# 3DR-GPS_mag-LEA6-v12.net
KiCad netlist of a schematic drawn in EAGLE
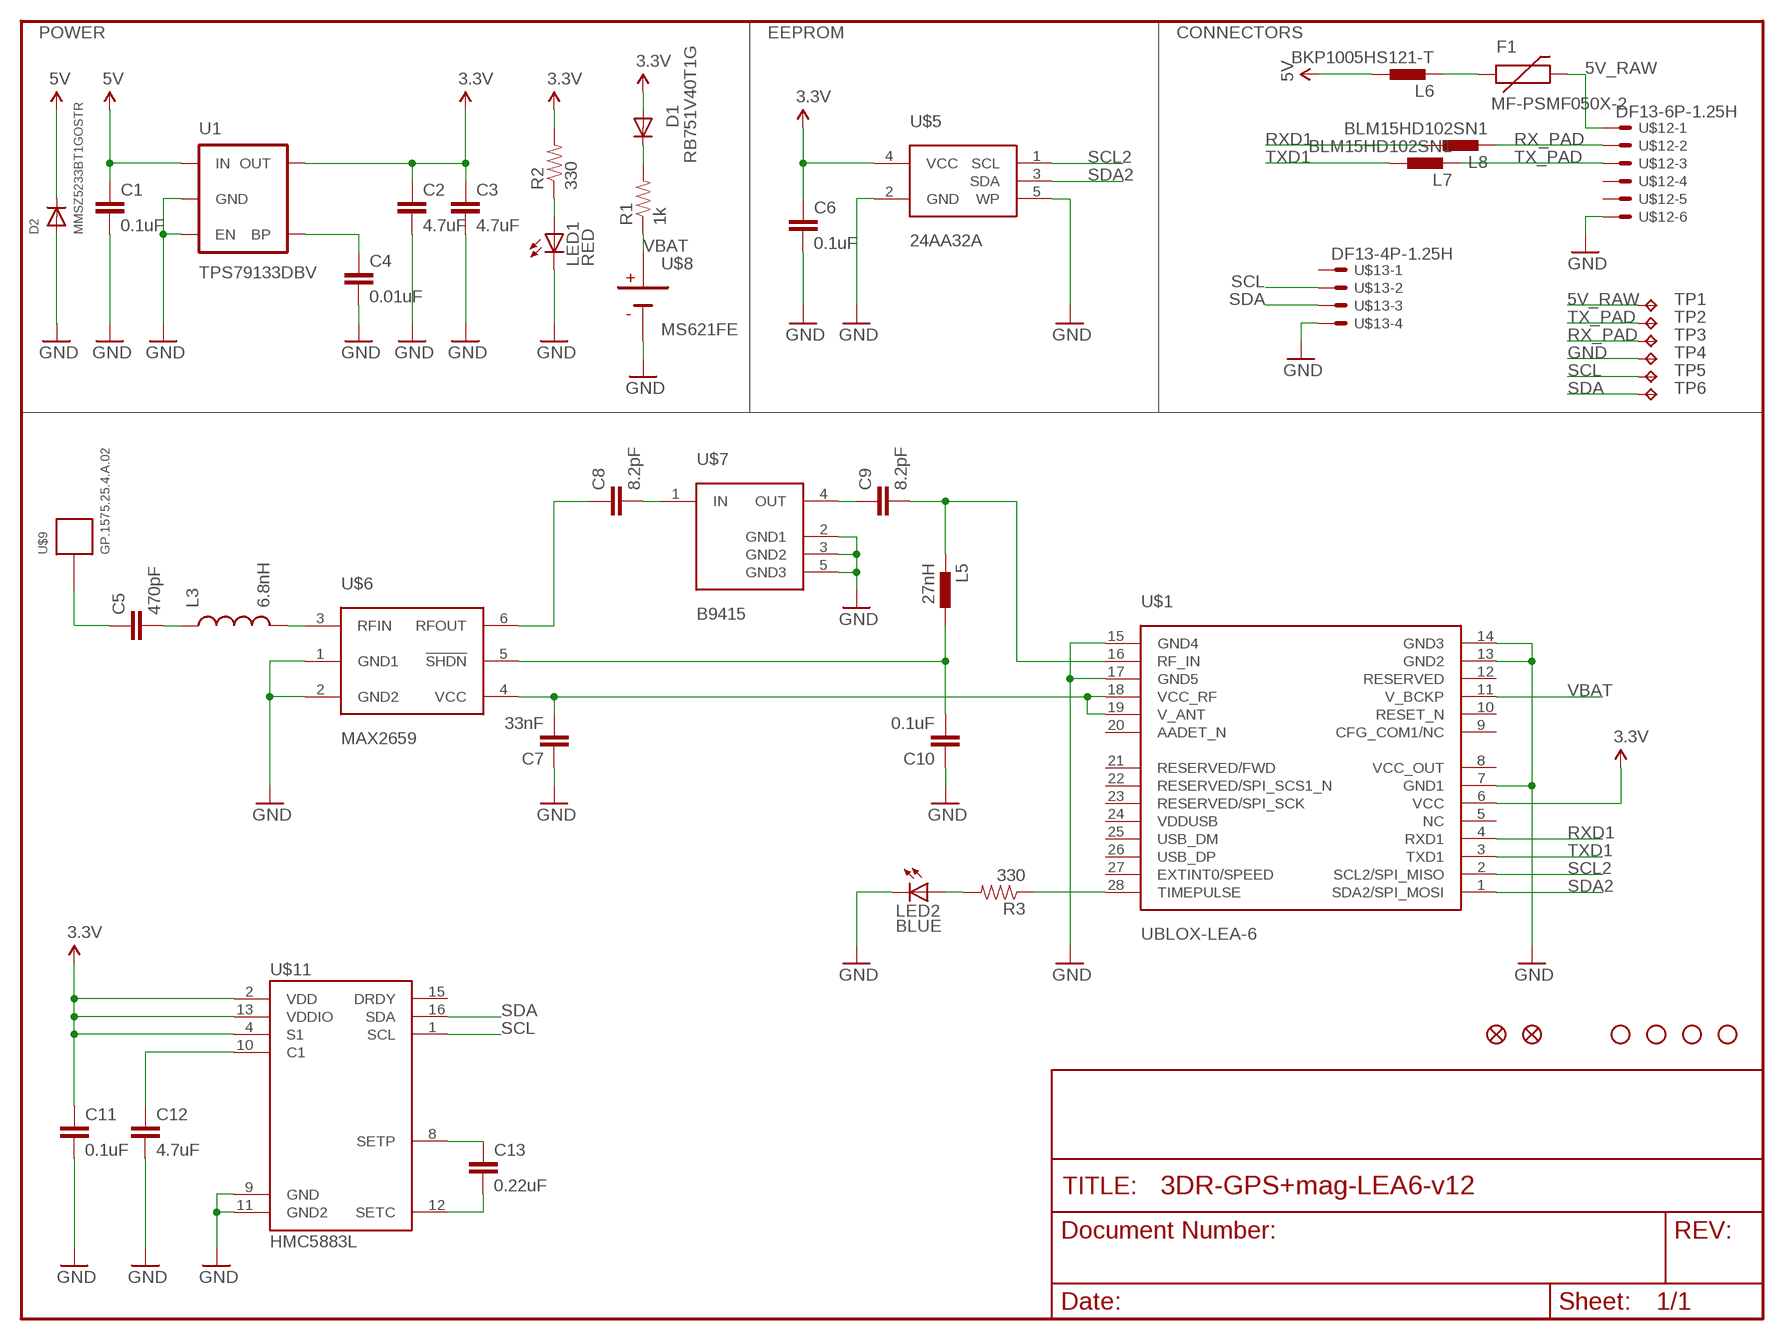
[diagram p0: schematic, sheet 1]

(export (version "E")
  (design (tool "Eeschema 10.0.6"))
  (components
    (comp (ref "C1")
      (value "0.1uF")
      (footprint "eagle-import:0402-CAP")
      (libsource (lib "eagle-import") (part "CAP0402-CAP"))
    )
    (comp (ref "C2")
      (value "4.7uF")
      (footprint "eagle-import:0805")
      (libsource (lib "eagle-import") (part "CAP0805"))
    )
    (comp (ref "C3")
      (value "4.7uF")
      (footprint "eagle-import:0805")
      (libsource (lib "eagle-import") (part "CAP0805"))
    )
    (comp (ref "C4")
      (value "0.01uF")
      (footprint "eagle-import:0402-CAP")
      (libsource (lib "eagle-import") (part "CAP0402-CAP"))
    )
    (comp (ref "C5")
      (value "470pF")
      (footprint "eagle-import:0402-CAP")
      (libsource (lib "eagle-import") (part "CAP0402-CAP"))
    )
    (comp (ref "C6")
      (value "0.1uF")
      (footprint "eagle-import:0402-CAP")
      (libsource (lib "eagle-import") (part "CAP0402-CAP"))
    )
    (comp (ref "C7")
      (value "33nF")
      (footprint "eagle-import:0402-CAP")
      (libsource (lib "eagle-import") (part "CAP0402-CAP"))
    )
    (comp (ref "C8")
      (value "8.2pF")
      (footprint "eagle-import:0402-CAP")
      (libsource (lib "eagle-import") (part "CAP0402-CAP"))
    )
    (comp (ref "C9")
      (value "8.2pF")
      (footprint "eagle-import:0402-CAP")
      (libsource (lib "eagle-import") (part "CAP0402-CAP"))
    )
    (comp (ref "C10")
      (value "0.1uF")
      (footprint "eagle-import:0402-CAP")
      (libsource (lib "eagle-import") (part "CAP0402-CAP"))
    )
    (comp (ref "C11")
      (value "0.1uF")
      (footprint "eagle-import:0402-CAP")
      (libsource (lib "eagle-import") (part "CAP0402-CAP"))
    )
    (comp (ref "C12")
      (value "4.7uF")
      (footprint "eagle-import:1206")
      (libsource (lib "eagle-import") (part "CAP1206"))
    )
    (comp (ref "C13")
      (value "0.22uF")
      (footprint "eagle-import:0402-CAP")
      (libsource (lib "eagle-import") (part "CAP0402-CAP"))
    )
    (comp (ref "D1")
      (value "RB751V40T1G")
      (footprint "eagle-import:SOD-323")
      (libsource (lib "eagle-import") (part "DIODESOD"))
    )
    (comp (ref "D2")
      (value "MMSZ5233BT1GOSTR")
      (footprint "eagle-import:SOD-123")
      (libsource (lib "eagle-import") (part "DIODESOD-123"))
    )
    (comp (ref "F1")
      (value "MF-PSMF050X-2")
      (footprint "eagle-import:0805")
      (libsource (lib "eagle-import") (part "PTC"))
    )
    (comp (ref "JP1")
      (value "FIDUCIAL1X2")
      (footprint "eagle-import:FIDUCIAL-1X2")
      (libsource (lib "eagle-import") (part "FIDUCIAL1X2"))
    )
    (comp (ref "JP2")
      (value "FIDUCIAL1X2")
      (footprint "eagle-import:FIDUCIAL-1X2")
      (libsource (lib "eagle-import") (part "FIDUCIAL1X2"))
    )
    (comp (ref "JP3")
      (value "STAND-OFF")
      (footprint "eagle-import:STAND-OFF")
      (libsource (lib "eagle-import") (part "STAND-OFF"))
    )
    (comp (ref "JP4")
      (value "STAND-OFF")
      (footprint "eagle-import:STAND-OFF")
      (libsource (lib "eagle-import") (part "STAND-OFF"))
    )
    (comp (ref "JP5")
      (value "STAND-OFF")
      (footprint "eagle-import:STAND-OFF")
      (libsource (lib "eagle-import") (part "STAND-OFF"))
    )
    (comp (ref "JP6")
      (value "STAND-OFF")
      (footprint "eagle-import:STAND-OFF")
      (libsource (lib "eagle-import") (part "STAND-OFF"))
    )
    (comp (ref "L3")
      (value "6.8nH")
      (footprint "eagle-import:C0402")
      (libsource (lib "eagle-import") (part "INDUCTOR0402"))
    )
    (comp (ref "L5")
      (value "27nH")
      (footprint "eagle-import:0402-IND")
      (libsource (lib "eagle-import") (part "INDUCTOR-0402"))
    )
    (comp (ref "L6")
      (value "BKP1005HS121-T")
      (footprint "eagle-import:0402-IND")
      (libsource (lib "eagle-import") (part "INDUCTOR-0402"))
    )
    (comp (ref "L7")
      (value "BLM15HD102SN1")
      (footprint "eagle-import:0402-IND")
      (libsource (lib "eagle-import") (part "INDUCTOR-0402"))
    )
    (comp (ref "L8")
      (value "BLM15HD102SN1")
      (footprint "eagle-import:0402-IND")
      (libsource (lib "eagle-import") (part "INDUCTOR-0402"))
    )
    (comp (ref "LED1")
      (value "RED")
      (footprint "eagle-import:LED-0603")
      (libsource (lib "eagle-import") (part "LED0603"))
    )
    (comp (ref "LED2")
      (value "BLUE")
      (footprint "eagle-import:LED-0603")
      (libsource (lib "eagle-import") (part "LED0603"))
    )
    (comp (ref "R1")
      (value "1k")
      (footprint "eagle-import:0402-RES")
      (libsource (lib "eagle-import") (part "RESISTOR0402-RES"))
    )
    (comp (ref "R2")
      (value "330")
      (footprint "eagle-import:0402-RES")
      (libsource (lib "eagle-import") (part "RESISTOR0402-RES"))
    )
    (comp (ref "R3")
      (value "330")
      (footprint "eagle-import:0402-RES")
      (libsource (lib "eagle-import") (part "RESISTOR0402-RES"))
    )
    (comp (ref "TP1")
      (value "TPTP20SQ")
      (footprint "eagle-import:TP20SQ")
      (libsource (lib "eagle-import") (part "TPTP20SQ"))
    )
    (comp (ref "TP2")
      (value "TPTP20SQ")
      (footprint "eagle-import:TP20SQ")
      (libsource (lib "eagle-import") (part "TPTP20SQ"))
    )
    (comp (ref "TP3")
      (value "TPTP20SQ")
      (footprint "eagle-import:TP20SQ")
      (libsource (lib "eagle-import") (part "TPTP20SQ"))
    )
    (comp (ref "TP4")
      (value "TPTP20SQ")
      (footprint "eagle-import:TP20SQ")
      (libsource (lib "eagle-import") (part "TPTP20SQ"))
    )
    (comp (ref "TP5")
      (value "TPTP20SQ")
      (footprint "eagle-import:TP20SQ")
      (libsource (lib "eagle-import") (part "TPTP20SQ"))
    )
    (comp (ref "TP6")
      (value "TPTP20SQ")
      (footprint "eagle-import:TP20SQ")
      (libsource (lib "eagle-import") (part "TPTP20SQ"))
    )
    (comp (ref "U$1")
      (value "UBLOX-LEA-6")
      (footprint "eagle-import:UBLOX-LEA")
      (libsource (lib "eagle-import") (part "UBLOX-LEA-6"))
    )
    (comp (ref "U$5")
      (value "24AA32A")
      (footprint "eagle-import:SOT23-5")
      (libsource (lib "eagle-import") (part "24AA32A"))
    )
    (comp (ref "U$6")
      (value "MAX2659")
      (footprint "eagle-import:UDFN-6")
      (libsource (lib "eagle-import") (part "MAX2659"))
    )
    (comp (ref "U$7")
      (value "B9415")
      (footprint "eagle-import:GPS-RF-SAW-FILTER")
      (fields (field (name "MFGPN") "B9415"))
      (libsource (lib "eagle-import") (part "B9415"))
    )
    (comp (ref "U$8")
      (value "MS621FE")
      (footprint "eagle-import:MS621FE")
      (libsource (lib "eagle-import") (part "MS621FE"))
    )
    (comp (ref "U$9")
      (value "GP.1575.25.4.A.02")
      (footprint "eagle-import:GP.1575.25.4.A.02")
      (libsource (lib "eagle-import") (part "GP.1575.25.4.A.02"))
    )
    (comp (ref "U$11")
      (value "HMC5883L")
      (footprint "eagle-import:LPCC16")
      (libsource (lib "eagle-import") (part "HMC5883L"))
    )
    (comp (ref "U$12")
      (value "DF13-6P-1.25H")
      (footprint "eagle-import:DF13A-6P-1.25H")
      (libsource (lib "eagle-import") (part "DF13-6P-1.25?H"))
    )
    (comp (ref "U$13")
      (value "DF13-4P-1.25H")
      (footprint "eagle-import:DF13A-4P-1.25H")
      (libsource (lib "eagle-import") (part "DF13-4P-1.25?H"))
    )
    (comp (ref "U1")
      (value "TPS79133DBV")
      (footprint "eagle-import:SOT23-5")
      (libsource (lib "eagle-import") (part "V_REG_LDOSMD"))
    )
  )
  (nets
    (net (code "1") (name "/5V_RAW") (class "Default")
      (node (ref "F1") (pin "2") (pinfunction "2_2") (pintype "bidirectional"))
      (node (ref "TP1") (pin "TP") (pinfunction "TP_TP") (pintype "input"))
      (node (ref "U$12") (pin "1") (pinfunction "S_1") (pintype "passive"))
    )
    (net (code "2") (name "/RXD1") (class "Default")
      (node (ref "L8") (pin "P$1") (pinfunction "1_P$1") (pintype "passive"))
      (node (ref "U$1") (pin "4") (pinfunction "RXD1_4") (pintype "bidirectional"))
    )
    (net (code "3") (name "/RX_PAD") (class "Default")
      (node (ref "L8") (pin "P$2") (pinfunction "2_P$2") (pintype "passive"))
      (node (ref "TP3") (pin "TP") (pinfunction "TP_TP") (pintype "input"))
      (node (ref "U$12") (pin "2") (pinfunction "S_2") (pintype "passive"))
    )
    (net (code "4") (name "/SCL") (class "Default")
      (node (ref "TP5") (pin "TP") (pinfunction "TP_TP") (pintype "input"))
      (node (ref "U$11") (pin "1") (pinfunction "SCL_1") (pintype "bidirectional"))
      (node (ref "U$13") (pin "2") (pinfunction "S_2") (pintype "passive"))
    )
    (net (code "5") (name "/SCL2") (class "Default")
      (node (ref "U$1") (pin "2") (pinfunction "SCL2/SPI_MISO_2") (pintype "bidirectional"))
      (node (ref "U$5") (pin "1") (pinfunction "SCL_1") (pintype "bidirectional"))
    )
    (net (code "6") (name "/SDA") (class "Default")
      (node (ref "TP6") (pin "TP") (pinfunction "TP_TP") (pintype "input"))
      (node (ref "U$11") (pin "16") (pinfunction "SDA_16") (pintype "bidirectional"))
      (node (ref "U$13") (pin "3") (pinfunction "S_3") (pintype "passive"))
    )
    (net (code "7") (name "/SDA2") (class "Default")
      (node (ref "U$1") (pin "1") (pinfunction "SDA2/SPI_MOSI_1") (pintype "bidirectional"))
      (node (ref "U$5") (pin "3") (pinfunction "SDA_3") (pintype "bidirectional"))
    )
    (net (code "8") (name "/TXD1") (class "Default")
      (node (ref "L7") (pin "P$1") (pinfunction "1_P$1") (pintype "passive"))
      (node (ref "U$1") (pin "3") (pinfunction "TXD1_3") (pintype "bidirectional"))
    )
    (net (code "9") (name "/TX_PAD") (class "Default")
      (node (ref "L7") (pin "P$2") (pinfunction "2_P$2") (pintype "passive"))
      (node (ref "TP2") (pin "TP") (pinfunction "TP_TP") (pintype "input"))
      (node (ref "U$12") (pin "3") (pinfunction "S_3") (pintype "passive"))
    )
    (net (code "10") (name "/VBAT") (class "Default")
      (node (ref "R1") (pin "1") (pinfunction "1_1") (pintype "passive"))
      (node (ref "U$1") (pin "11") (pinfunction "V_BCKP_11") (pintype "bidirectional"))
      (node (ref "U$8") (pin "1") (pinfunction "POS_1") (pintype "bidirectional"))
    )
    (net (code "11") (name "3.3V") (class "Default")
      (node (ref "C11") (pin "1") (pinfunction "1_1") (pintype "passive"))
      (node (ref "C2") (pin "1") (pinfunction "1_1") (pintype "passive"))
      (node (ref "C3") (pin "1") (pinfunction "1_1") (pintype "passive"))
      (node (ref "C6") (pin "1") (pinfunction "1_1") (pintype "passive"))
      (node (ref "D1") (pin "2") (pinfunction "A_2") (pintype "passive"))
      (node (ref "R2") (pin "2") (pinfunction "2_2") (pintype "passive"))
      (node (ref "U$1") (pin "6") (pinfunction "VCC_6") (pintype "bidirectional"))
      (node (ref "U$11") (pin "13") (pinfunction "VDDIO_13") (pintype "bidirectional"))
      (node (ref "U$11") (pin "2") (pinfunction "VDD_2") (pintype "bidirectional"))
      (node (ref "U$11") (pin "4") (pinfunction "S1_4") (pintype "bidirectional"))
      (node (ref "U$5") (pin "4") (pinfunction "VCC_4") (pintype "bidirectional"))
      (node (ref "U1") (pin "5") (pinfunction "OUT_5") (pintype "passive"))
    )
    (net (code "12") (name "5V") (class "Default")
      (node (ref "C1") (pin "1") (pinfunction "1_1") (pintype "passive"))
      (node (ref "D2") (pin "C") (pinfunction "C_C") (pintype "passive"))
      (node (ref "L6") (pin "P$1") (pinfunction "1_P$1") (pintype "passive"))
      (node (ref "U1") (pin "1") (pinfunction "IN_1") (pintype "input"))
    )
    (net (code "13") (name "GND") (class "Default")
      (node (ref "C1") (pin "2") (pinfunction "2_2") (pintype "passive"))
      (node (ref "C10") (pin "1") (pinfunction "1_1") (pintype "passive"))
      (node (ref "C11") (pin "2") (pinfunction "2_2") (pintype "passive"))
      (node (ref "C12") (pin "2") (pinfunction "2_2") (pintype "passive"))
      (node (ref "C2") (pin "2") (pinfunction "2_2") (pintype "passive"))
      (node (ref "C3") (pin "2") (pinfunction "2_2") (pintype "passive"))
      (node (ref "C4") (pin "2") (pinfunction "2_2") (pintype "passive"))
      (node (ref "C6") (pin "2") (pinfunction "2_2") (pintype "passive"))
      (node (ref "C7") (pin "1") (pinfunction "1_1") (pintype "passive"))
      (node (ref "D2") (pin "A") (pinfunction "A_A") (pintype "passive"))
      (node (ref "LED1") (pin "C") (pinfunction "C_C") (pintype "passive"))
      (node (ref "LED2") (pin "C") (pinfunction "C_C") (pintype "passive"))
      (node (ref "TP4") (pin "TP") (pinfunction "TP_TP") (pintype "input"))
      (node (ref "U$1") (pin "13") (pinfunction "GND2_13") (pintype "bidirectional"))
      (node (ref "U$1") (pin "14") (pinfunction "GND3_14") (pintype "bidirectional"))
      (node (ref "U$1") (pin "15") (pinfunction "GND4_15") (pintype "bidirectional"))
      (node (ref "U$1") (pin "17") (pinfunction "GND5_17") (pintype "bidirectional"))
      (node (ref "U$1") (pin "7") (pinfunction "GND1_7") (pintype "bidirectional"))
      (node (ref "U$11") (pin "11") (pinfunction "GND2_11") (pintype "bidirectional"))
      (node (ref "U$11") (pin "9") (pinfunction "GND_9") (pintype "bidirectional"))
      (node (ref "U$12") (pin "6") (pinfunction "S_6") (pintype "passive"))
      (node (ref "U$13") (pin "4") (pinfunction "S_4") (pintype "passive"))
      (node (ref "U$5") (pin "2") (pinfunction "GND_2") (pintype "bidirectional"))
      (node (ref "U$5") (pin "5") (pinfunction "WP_5") (pintype "bidirectional"))
      (node (ref "U$6") (pin "1") (pinfunction "GND1_1") (pintype "bidirectional"))
      (node (ref "U$6") (pin "2") (pinfunction "GND2_2") (pintype "bidirectional"))
      (node (ref "U$7") (pin "2") (pinfunction "GND1_2") (pintype "bidirectional"))
      (node (ref "U$7") (pin "3") (pinfunction "GND2_3") (pintype "bidirectional"))
      (node (ref "U$7") (pin "5") (pinfunction "GND3_5") (pintype "bidirectional"))
      (node (ref "U$8") (pin "2") (pinfunction "NEG_2") (pintype "bidirectional"))
      (node (ref "U1") (pin "2") (pinfunction "GND_2") (pintype "input"))
      (node (ref "U1") (pin "3") (pinfunction "EN_3") (pintype "input"))
    )
    (net (code "14") (name "Net-(C5-Pad2)") (class "Default")
      (node (ref "C5") (pin "2") (pinfunction "2_2") (pintype "passive"))
      (node (ref "L3") (pin "1") (pinfunction "1_1") (pintype "passive"))
    )
    (net (code "15") (name "Net-(D1-C)") (class "Default")
      (node (ref "D1") (pin "1") (pinfunction "C_1") (pintype "passive"))
      (node (ref "R1") (pin "2") (pinfunction "2_2") (pintype "passive"))
    )
    (net (code "16") (name "Net-(L5-1)") (class "Default")
      (node (ref "C10") (pin "2") (pinfunction "2_2") (pintype "passive"))
      (node (ref "L5") (pin "P$1") (pinfunction "1_P$1") (pintype "passive"))
      (node (ref "U$6") (pin "5") (pinfunction "~{SHDN}_5") (pintype "bidirectional"))
    )
    (net (code "17") (name "Net-(L5-2)") (class "Default")
      (node (ref "C9") (pin "2") (pinfunction "2_2") (pintype "passive"))
      (node (ref "L5") (pin "P$2") (pinfunction "2_P$2") (pintype "passive"))
      (node (ref "U$1") (pin "16") (pinfunction "RF_IN_16") (pintype "bidirectional"))
    )
    (net (code "18") (name "Net-(L6-2)") (class "Default")
      (node (ref "F1") (pin "1") (pinfunction "1_1") (pintype "bidirectional"))
      (node (ref "L6") (pin "P$2") (pinfunction "2_P$2") (pintype "passive"))
    )
    (net (code "19") (name "Net-(LED1-PadA)") (class "Default")
      (node (ref "LED1") (pin "A") (pinfunction "A_A") (pintype "passive"))
      (node (ref "R2") (pin "1") (pinfunction "1_1") (pintype "passive"))
    )
    (net (code "20") (name "Net-(LED2-PadA)") (class "Default")
      (node (ref "LED2") (pin "A") (pinfunction "A_A") (pintype "passive"))
      (node (ref "R3") (pin "2") (pinfunction "2_2") (pintype "passive"))
    )
    (net (code "21") (name "Net-(U$1-TIMEPULSE)") (class "Default")
      (node (ref "R3") (pin "1") (pinfunction "1_1") (pintype "passive"))
      (node (ref "U$1") (pin "28") (pinfunction "TIMEPULSE_28") (pintype "bidirectional"))
    )
    (net (code "22") (name "Net-(U$1-VCC_RF)") (class "Default")
      (node (ref "C7") (pin "2") (pinfunction "2_2") (pintype "passive"))
      (node (ref "U$1") (pin "18") (pinfunction "VCC_RF_18") (pintype "bidirectional"))
      (node (ref "U$1") (pin "19") (pinfunction "V_ANT_19") (pintype "bidirectional"))
      (node (ref "U$6") (pin "4") (pinfunction "VCC_4") (pintype "bidirectional"))
    )
    (net (code "23") (name "Net-(U$6-RFIN)") (class "Default")
      (node (ref "L3") (pin "2") (pinfunction "2_2") (pintype "passive"))
      (node (ref "U$6") (pin "3") (pinfunction "RFIN_3") (pintype "bidirectional"))
    )
    (net (code "24") (name "Net-(U$6-RFOUT)") (class "Default")
      (node (ref "C8") (pin "1") (pinfunction "1_1") (pintype "passive"))
      (node (ref "U$6") (pin "6") (pinfunction "RFOUT_6") (pintype "bidirectional"))
    )
    (net (code "25") (name "Net-(U$7-IN)") (class "Default")
      (node (ref "C8") (pin "2") (pinfunction "2_2") (pintype "passive"))
      (node (ref "U$7") (pin "1") (pinfunction "IN_1") (pintype "bidirectional"))
    )
    (net (code "26") (name "Net-(U$7-OUT)") (class "Default")
      (node (ref "C9") (pin "1") (pinfunction "1_1") (pintype "passive"))
      (node (ref "U$7") (pin "4") (pinfunction "OUT_4") (pintype "bidirectional"))
    )
    (net (code "27") (name "Net-(U$9-PIN)") (class "Default")
      (node (ref "C5") (pin "1") (pinfunction "1_1") (pintype "passive"))
      (node (ref "U$9") (pin "1") (pinfunction "PIN_1") (pintype "bidirectional"))
    )
    (net (code "28") (name "Net-(U$11-C1)") (class "Default")
      (node (ref "C12") (pin "1") (pinfunction "1_1") (pintype "passive"))
      (node (ref "U$11") (pin "10") (pinfunction "C1_10") (pintype "bidirectional"))
    )
    (net (code "29") (name "Net-(U$11-SETC)") (class "Default")
      (node (ref "C13") (pin "2") (pinfunction "2_2") (pintype "passive"))
      (node (ref "U$11") (pin "12") (pinfunction "SETC_12") (pintype "bidirectional"))
    )
    (net (code "30") (name "Net-(U$11-SETP)") (class "Default")
      (node (ref "C13") (pin "1") (pinfunction "1_1") (pintype "passive"))
      (node (ref "U$11") (pin "8") (pinfunction "SETP_8") (pintype "bidirectional"))
    )
    (net (code "31") (name "Net-(U1-BP)") (class "Default")
      (node (ref "C4") (pin "1") (pinfunction "1_1") (pintype "passive"))
      (node (ref "U1") (pin "4") (pinfunction "BP_4") (pintype "input"))
    )
    (net (code "32") (name "unconnected-(U$1-AADET_N-Pad20)") (class "Default")
      (node (ref "U$1") (pin "20") (pinfunction "AADET_N_20") (pintype "bidirectional"))
    )
    (net (code "33") (name "unconnected-(U$1-CFG_COM1{slash}NC-Pad9)") (class "Default")
      (node (ref "U$1") (pin "9") (pinfunction "CFG_COM1/NC_9") (pintype "bidirectional"))
    )
    (net (code "34") (name "unconnected-(U$1-EXTINT0{slash}SPEED-Pad27)") (class "Default")
      (node (ref "U$1") (pin "27") (pinfunction "EXTINT0/SPEED_27") (pintype "bidirectional"))
    )
    (net (code "35") (name "unconnected-(U$1-NC-Pad5)") (class "Default")
      (node (ref "U$1") (pin "5") (pinfunction "NC_5") (pintype "bidirectional"))
    )
    (net (code "36") (name "unconnected-(U$1-RESERVED-Pad12)") (class "Default")
      (node (ref "U$1") (pin "12") (pinfunction "RESERVED_12") (pintype "bidirectional"))
    )
    (net (code "37") (name "unconnected-(U$1-RESERVED{slash}FWD-Pad21)") (class "Default")
      (node (ref "U$1") (pin "21") (pinfunction "RESERVED/FWD_21") (pintype "bidirectional"))
    )
    (net (code "38") (name "unconnected-(U$1-RESERVED{slash}SPI_SCK-Pad23)") (class "Default")
      (node (ref "U$1") (pin "23") (pinfunction "RESERVED/SPI_SCK_23") (pintype "bidirectional"))
    )
    (net (code "39") (name "unconnected-(U$1-RESERVED{slash}SPI_SCS1_N-Pad22)") (class "Default")
      (node (ref "U$1") (pin "22") (pinfunction "RESERVED/SPI_SCS1_N_22") (pintype "bidirectional"))
    )
    (net (code "40") (name "unconnected-(U$1-RESET_N-Pad10)") (class "Default")
      (node (ref "U$1") (pin "10") (pinfunction "RESET_N_10") (pintype "bidirectional"))
    )
    (net (code "41") (name "unconnected-(U$1-USB_DM-Pad25)") (class "Default")
      (node (ref "U$1") (pin "25") (pinfunction "USB_DM_25") (pintype "bidirectional"))
    )
    (net (code "42") (name "unconnected-(U$1-USB_DP-Pad26)") (class "Default")
      (node (ref "U$1") (pin "26") (pinfunction "USB_DP_26") (pintype "bidirectional"))
    )
    (net (code "43") (name "unconnected-(U$1-VCC_OUT-Pad8)") (class "Default")
      (node (ref "U$1") (pin "8") (pinfunction "VCC_OUT_8") (pintype "bidirectional"))
    )
    (net (code "44") (name "unconnected-(U$1-VDDUSB-Pad24)") (class "Default")
      (node (ref "U$1") (pin "24") (pinfunction "VDDUSB_24") (pintype "bidirectional"))
    )
    (net (code "45") (name "unconnected-(U$11-DRDY-Pad15)") (class "Default")
      (node (ref "U$11") (pin "15") (pinfunction "DRDY_15") (pintype "bidirectional"))
    )
    (net (code "46") (name "unconnected-(U$12D-S-Pad4)") (class "Default")
      (node (ref "U$12") (pin "4") (pinfunction "S_4") (pintype "passive"))
    )
    (net (code "47") (name "unconnected-(U$12E-S-Pad5)") (class "Default")
      (node (ref "U$12") (pin "5") (pinfunction "S_5") (pintype "passive"))
    )
    (net (code "48") (name "unconnected-(U$13A-S-Pad1)") (class "Default")
      (node (ref "U$13") (pin "1") (pinfunction "S_1") (pintype "passive"))
    )
  )
)
